# Ad_Hoc_Radio_Node_2005_v3.net
KiCad netlist of a schematic drawn in Altium Designer
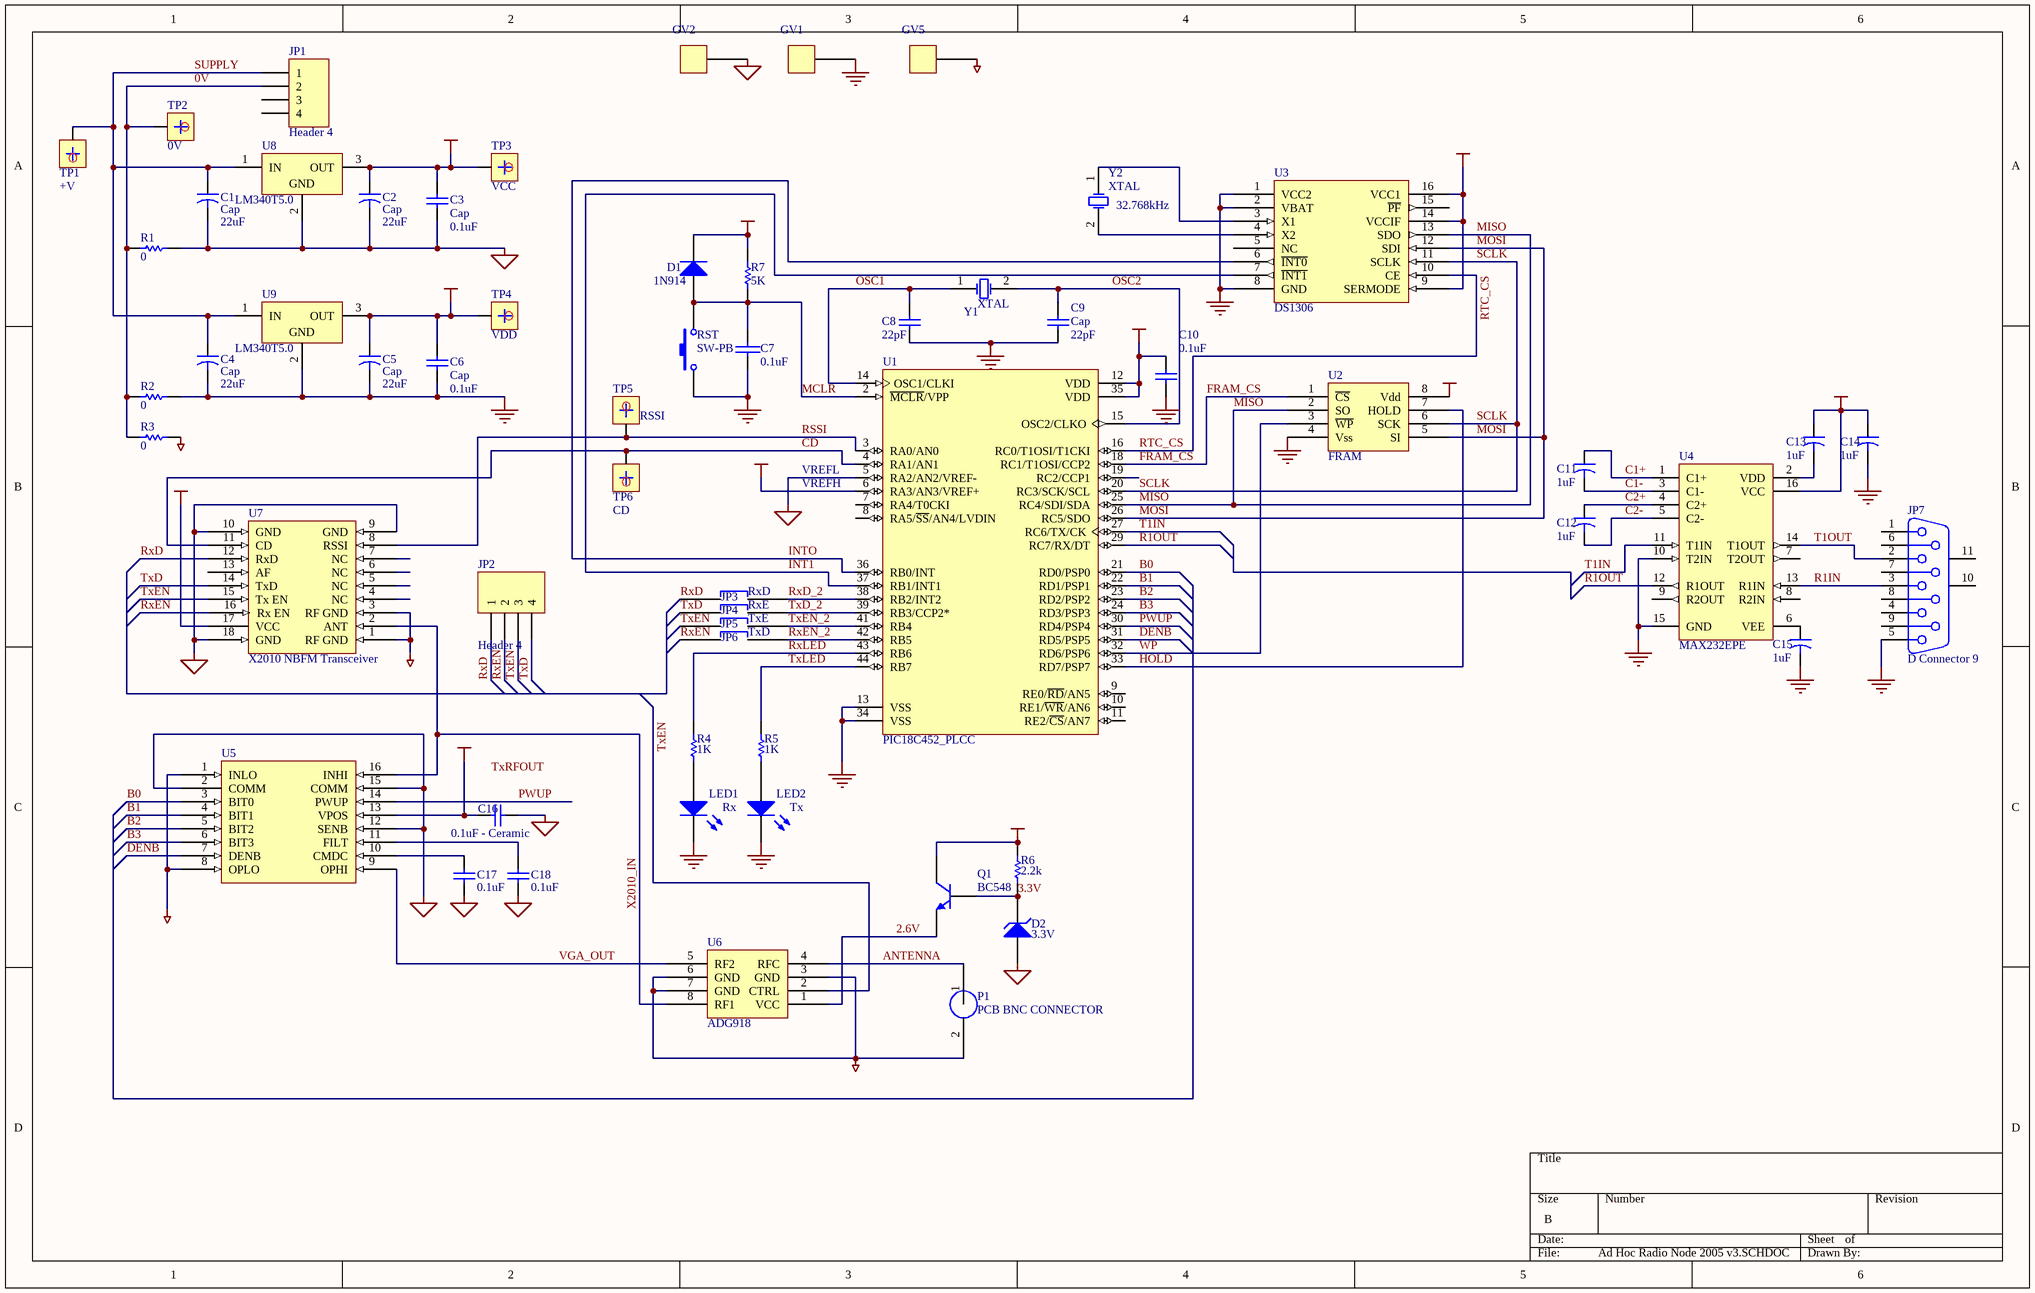
[diagram p0: Ad Hoc Radio Node 2005 v3.SCHDOC]

(export (version "E")
  (design (tool "Eeschema 10.0.6"))
  (components
    (comp (ref "C1")
      (value "Cap")
      (footprint "0.1 ELECTRO CAP")
      (description "Capacitor")
      (fields
        (field (name "MANUFACTURER") "Generic Components")
        (field (name "ALTIUM_VALUE") "22uF")
        (field (name "PUBLISHER") "Altium Limited")
      )
      (libsource (lib "Miscellaneous Devices") (part "Cap2"))
    )
    (comp (ref "C2")
      (value "Cap")
      (footprint "0.1 ELECTRO CAP")
      (description "Capacitor")
      (fields
        (field (name "MANUFACTURER") "Generic Components")
        (field (name "ALTIUM_VALUE") "22uF")
        (field (name "PUBLISHER") "Altium Limited")
      )
      (libsource (lib "Miscellaneous Devices") (part "Cap2"))
    )
    (comp (ref "C3")
      (value "Cap")
      (footprint "0.2 box cap")
      (description "Capacitor")
      (fields
        (field (name "MANUFACTURER") "Generic Components")
        (field (name "ALTIUM_VALUE") "0.1uF")
        (field (name "PUBLISHER") "Altium Limited")
      )
      (libsource (lib "Miscellaneous Devices") (part "Cap"))
    )
    (comp (ref "C4")
      (value "Cap")
      (footprint "0.1 ELECTRO CAP")
      (description "Capacitor")
      (fields
        (field (name "MANUFACTURER") "Generic Components")
        (field (name "ALTIUM_VALUE") "22uF")
        (field (name "PUBLISHER") "Altium Limited")
      )
      (libsource (lib "Miscellaneous Devices") (part "Cap2"))
    )
    (comp (ref "C5")
      (value "Cap")
      (footprint "0.1 ELECTRO CAP")
      (description "Capacitor")
      (fields
        (field (name "MANUFACTURER") "Generic Components")
        (field (name "ALTIUM_VALUE") "22uF")
        (field (name "PUBLISHER") "Altium Limited")
      )
      (libsource (lib "Miscellaneous Devices") (part "Cap2"))
    )
    (comp (ref "C6")
      (value "Cap")
      (footprint "0.2 box cap")
      (description "Capacitor")
      (fields
        (field (name "MANUFACTURER") "Generic Components")
        (field (name "ALTIUM_VALUE") "0.1uF")
        (field (name "PUBLISHER") "Altium Limited")
      )
      (libsource (lib "Miscellaneous Devices") (part "Cap"))
    )
    (comp (ref "C7")
      (value "0.1uF")
      (footprint "0.2 box cap")
      (description "Capacitor")
      (libsource (lib "*") (part "CAP"))
    )
    (comp (ref "C8")
      (value "Cap")
      (footprint "0.2 box cap")
      (description "Capacitor")
      (fields
        (field (name "MANUFACTURER") "Generic Components")
        (field (name "ALTIUM_VALUE") "22pF")
        (field (name "PUBLISHER") "Altium Limited")
      )
      (libsource (lib "Miscellaneous Devices") (part "Cap"))
    )
    (comp (ref "C9")
      (value "Cap")
      (footprint "0.2 box cap")
      (description "Capacitor")
      (fields
        (field (name "MANUFACTURER") "Generic Components")
        (field (name "ALTIUM_VALUE") "22pF")
        (field (name "PUBLISHER") "Altium Limited")
      )
      (libsource (lib "Miscellaneous Devices") (part "Cap"))
    )
    (comp (ref "C10")
      (value "0.1uF")
      (footprint "0.2 box cap")
      (description "Capacitor")
      (fields (field (name "MANUFACTURER") "Generic Components") (field (name "PUBLISHER") "Altium Limited"))
      (libsource (lib "Miscellaneous Devices") (part "Cap"))
    )
    (comp (ref "C11")
      (value "Cap2")
      (footprint "0.1 ELECTRO CAP")
      (description "Capacitor")
      (fields
        (field (name "MANUFACTURER") "Generic Components")
        (field (name "ALTIUM_VALUE") "1uF")
        (field (name "PUBLISHER") "Altium Limited")
      )
      (libsource (lib "Miscellaneous Devices") (part "Cap2"))
    )
    (comp (ref "C12")
      (value "Cap2")
      (footprint "0.1 ELECTRO CAP")
      (description "Capacitor")
      (fields
        (field (name "MANUFACTURER") "Generic Components")
        (field (name "ALTIUM_VALUE") "1uF")
        (field (name "PUBLISHER") "Altium Limited")
      )
      (libsource (lib "Miscellaneous Devices") (part "Cap2"))
    )
    (comp (ref "C13")
      (value "Cap2")
      (footprint "0.1 ELECTRO CAP")
      (description "Capacitor")
      (fields
        (field (name "MANUFACTURER") "Generic Components")
        (field (name "ALTIUM_VALUE") "1uF")
        (field (name "PUBLISHER") "Altium Limited")
      )
      (libsource (lib "Miscellaneous Devices") (part "Cap2"))
    )
    (comp (ref "C14")
      (value "Cap2")
      (footprint "0.1 ELECTRO CAP")
      (description "Capacitor")
      (fields
        (field (name "MANUFACTURER") "Generic Components")
        (field (name "ALTIUM_VALUE") "1uF")
        (field (name "PUBLISHER") "Altium Limited")
      )
      (libsource (lib "Miscellaneous Devices") (part "Cap2"))
    )
    (comp (ref "C15")
      (value "Cap2")
      (footprint "0.1 ELECTRO CAP")
      (description "Capacitor")
      (fields
        (field (name "MANUFACTURER") "Generic Components")
        (field (name "ALTIUM_VALUE") "1uF")
        (field (name "PUBLISHER") "Altium Limited")
      )
      (libsource (lib "Miscellaneous Devices") (part "Cap2"))
    )
    (comp (ref "C16")
      (value "0.1uF - Ceramic")
      (footprint "0.2 box cap")
      (description "Capacitor")
      (fields (field (name "MANUFACTURER") "Generic Components") (field (name "PUBLISHER") "Altium Limited"))
      (libsource (lib "Miscellaneous Devices") (part "Cap"))
    )
    (comp (ref "C17")
      (value "0.1uF")
      (footprint "0.2 box cap")
      (description "Capacitor")
      (fields (field (name "MANUFACTURER") "Generic Components") (field (name "PUBLISHER") "Altium Limited"))
      (libsource (lib "Miscellaneous Devices") (part "Cap"))
    )
    (comp (ref "C18")
      (value "0.1uF")
      (footprint "0.2 box cap")
      (description "Capacitor")
      (fields (field (name "MANUFACTURER") "Generic Components") (field (name "PUBLISHER") "Altium Limited"))
      (libsource (lib "Miscellaneous Devices") (part "Cap"))
    )
    (comp (ref "D1")
      (value "1N914")
      (footprint "diode-0.4/1.8")
      (description "Default Diode")
      (fields (field (name "MANUFACTURER") "Generic Components") (field (name "PUBLISHER") "Altium Limited"))
      (libsource (lib "Miscellaneous Devices") (part "Diode"))
    )
    (comp (ref "D2")
      (value "D Zener")
      (footprint "diode-0.4/1.8")
      (description "Zener Diode")
      (fields
        (field (name "MANUFACTURER") "Generic Components")
        (field (name "ALTIUM_VALUE") "3.3V")
        (field (name "PUBLISHER") "Altium Limited")
      )
      (libsource (lib "Miscellaneous Devices") (part "D Zener"))
    )
    (comp (ref "GV1") (value "GV") (footprint "GROUNDVIA") (libsource (lib "2005Parts") (part "GV")))
    (comp (ref "GV2") (value "GV") (footprint "GROUNDVIA") (libsource (lib "2005Parts") (part "GV")))
    (comp (ref "GV5") (value "GV") (footprint "GROUNDVIA") (libsource (lib "2005Parts") (part "GV")))
    (comp (ref "JP1")
      (value "Header 4")
      (footprint "4 Way Terminal Block")
      (description "Header, 4-Pin")
      (fields (field (name "MANUFACTURER") "Generic Components") (field (name "PUBLISHER") "Altium Limited"))
      (libsource (lib "Miscellaneous Connectors") (part "Header 4"))
    )
    (comp (ref "JP2")
      (value "Header 4")
      (footprint "4 Way Terminal Block")
      (description "Header, 4-Pin")
      (fields (field (name "MANUFACTURER") "Generic Components") (field (name "PUBLISHER") "Altium Limited"))
      (libsource (lib "") (part "Header 4_1"))
    )
    (comp (ref "JP3") (value "RxD") (footprint "JUMPER") (libsource (lib "2005Parts") (part "JUMPER")))
    (comp (ref "JP4") (value "RxE") (footprint "JUMPER") (libsource (lib "2005Parts") (part "JUMPER")))
    (comp (ref "JP5") (value "TxE") (footprint "JUMPER") (libsource (lib "2005Parts") (part "JUMPER")))
    (comp (ref "JP6") (value "TxD") (footprint "JUMPER") (libsource (lib "2005Parts") (part "JUMPER")))
    (comp (ref "JP7")
      (value "D Connector 9")
      (footprint "DSUB1.385-2H9")
      (description "Receptacle Assembly, 9 Position, Right Angle")
      (fields (field (name "MANUFACTURER") "Generic Components") (field (name "PUBLISHER") "Altium Limited"))
      (libsource (lib "Miscellaneous Connectors") (part "D Connector 9"))
    )
    (comp (ref "LED1")
      (value "Rx")
      (footprint "Std LED")
      (description "Typical RED, GREEN, YELLOW, AMBER GaAs LED")
      (fields (field (name "MANUFACTURER") "Generic Components") (field (name "PUBLISHER") "Altium Limited"))
      (libsource (lib "Miscellaneous Devices") (part "LED2"))
    )
    (comp (ref "LED2")
      (value "Tx")
      (footprint "Std LED")
      (description "Typical RED, GREEN, YELLOW, AMBER GaAs LED")
      (fields (field (name "MANUFACTURER") "Generic Components") (field (name "PUBLISHER") "Altium Limited"))
      (libsource (lib "Miscellaneous Devices") (part "LED2"))
    )
    (comp (ref "P1")
      (value "PCB BNC CONNECTOR")
      (footprint "PCB BNC Connector")
      (libsource (lib "2005Parts") (part "PCB BNC CONNECTOR"))
    )
    (comp (ref "Q1")
      (value "BC548")
      (footprint "bjt")
      (description "NPN Bipolar Transistor")
      (fields (field (name "MANUFACTURER") "Generic Components") (field (name "PUBLISHER") "Altium Limited"))
      (libsource (lib "Miscellaneous Devices") (part "NPN"))
    )
    (comp (ref "R1")
      (value "0")
      (footprint "AXIAL-0.3")
      (description "Resistor")
      (fields (field (name "MANUFACTURER") "Generic Components") (field (name "PUBLISHER") "Altium Limited"))
      (libsource (lib "Miscellaneous Devices") (part "Res1"))
    )
    (comp (ref "R2")
      (value "0")
      (footprint "AXIAL-0.3")
      (description "Resistor")
      (fields (field (name "MANUFACTURER") "Generic Components") (field (name "PUBLISHER") "Altium Limited"))
      (libsource (lib "Miscellaneous Devices") (part "Res1"))
    )
    (comp (ref "R3")
      (value "0")
      (footprint "AXIAL-0.3")
      (description "Resistor")
      (fields (field (name "MANUFACTURER") "Generic Components") (field (name "PUBLISHER") "Altium Limited"))
      (libsource (lib "Miscellaneous Devices") (part "Res1"))
    )
    (comp (ref "R4")
      (value "1K")
      (footprint "AXIAL-0.4/1.8")
      (description "Resistor")
      (fields (field (name "MANUFACTURER") "Generic Components") (field (name "PUBLISHER") "Altium Limited"))
      (libsource (lib "Miscellaneous Devices") (part "Res1"))
    )
    (comp (ref "R5")
      (value "1K")
      (footprint "AXIAL-0.4/1.8")
      (description "Resistor")
      (fields (field (name "MANUFACTURER") "Generic Components") (field (name "PUBLISHER") "Altium Limited"))
      (libsource (lib "Miscellaneous Devices") (part "Res1"))
    )
    (comp (ref "R6")
      (value "2.2k")
      (footprint "AXIAL-0.4/1.8")
      (description "Resistor")
      (fields (field (name "MANUFACTURER") "Generic Components") (field (name "PUBLISHER") "Altium Limited"))
      (libsource (lib "Miscellaneous Devices") (part "Res1"))
    )
    (comp (ref "R7")
      (value "Res1")
      (footprint "AXIAL-0.4/1.8")
      (description "Resistor")
      (fields
        (field (name "MANUFACTURER") "Generic Components")
        (field (name "ALTIUM_VALUE") "5K")
        (field (name "PUBLISHER") "Altium Limited")
      )
      (libsource (lib "Miscellaneous Devices") (part "Res1"))
    )
    (comp (ref "RST")
      (value "SW-PB")
      (footprint "Reset Switch - duplicate")
      (description "Switch")
      (fields (field (name "MANUFACTURER") "Generic Components") (field (name "PUBLISHER") "Altium Limited"))
      (libsource (lib "Miscellaneous Devices") (part "SW-PB"))
    )
    (comp (ref "TP1")
      (value "+V")
      (footprint "TESTPOINT")
      (description "Test Point")
      (libsource (lib "") (part "TESTPOINT_1"))
    )
    (comp (ref "TP2")
      (value "0V")
      (footprint "TESTPOINT")
      (description "Test Point")
      (libsource (lib "PeteSchLib") (part "TESTPOINT"))
    )
    (comp (ref "TP3")
      (value "VCC")
      (footprint "TESTPOINT")
      (description "Test Point")
      (libsource (lib "PeteSchLib") (part "TESTPOINT"))
    )
    (comp (ref "TP4")
      (value "VDD")
      (footprint "TESTPOINT")
      (description "Test Point")
      (libsource (lib "PeteSchLib") (part "TESTPOINT"))
    )
    (comp (ref "TP5")
      (value "RSSI")
      (footprint "TESTPOINT")
      (description "Test Point")
      (libsource (lib "") (part "TESTPOINT_2"))
    )
    (comp (ref "TP6")
      (value "CD")
      (footprint "TESTPOINT")
      (description "Test Point")
      (libsource (lib "") (part "TESTPOINT_1"))
    )
    (comp (ref "U1")
      (value "PIC18C452_PLCC")
      (footprint "PIC18C452_PLCC - duplicate")
      (libsource (lib "Ad_Hoc_Parts") (part "PIC18C452_PLCC"))
    )
    (comp (ref "U2") (value "FRAM") (footprint "Ramtron FRAM") (libsource (lib "Ad_Hoc_Parts") (part "FRAM")))
    (comp (ref "U3") (value "DS1306") (footprint "DIP-16") (libsource (lib "2005Parts") (part "DS1306")))
    (comp (ref "U4")
      (value "MAX232EPE")
      (footprint "DIP-16")
      (description "+5V Powered RS-232 Driver/Receiver")
      (fields (field (name "MANUFACTURER") "Maxim") (field (name "PUBLISHER") "Altium Limited"))
      (libsource (lib "Maxim Communication Transceiver") (part "MAX232EPE"))
    )
    (comp (ref "U5")
      (value "~")
      (footprint "DIP16-Adaptor")
      (libsource (lib "Ad_Hoc_Parts") (part "AD8369_DIGITAL_CONT_PWR_AMP"))
    )
    (comp (ref "U6") (value "ADG918") (footprint "DIP-8") (libsource (lib "2005Parts") (part "ADG918")))
    (comp (ref "U7")
      (value "X2010 NBFM Transceiver")
      (footprint "X2010")
      (libsource (lib "Ad_Hoc_Parts") (part "NBFM_TRANSCEIVER"))
    )
    (comp (ref "U8")
      (value "LM340T5.0")
      (footprint "SFM-T3/A4.7V")
      (description "Series 3-Terminal Positive Regulator")
      (fields
        (field (name "MANUFACTURER") "National Semiconductor")
        (field (name "PUBLISHER") "Altium Limited")
      )
      (libsource (lib "NSC Power Mgt Voltage Regulator") (part "LM340T5.0"))
    )
    (comp (ref "U9")
      (value "LM340T5.0")
      (footprint "SFM-T3/A4.7V")
      (description "Series 3-Terminal Positive Regulator")
      (fields
        (field (name "MANUFACTURER") "National Semiconductor")
        (field (name "PUBLISHER") "Altium Limited")
      )
      (libsource (lib "NSC Power Mgt Voltage Regulator") (part "LM340T5.0"))
    )
    (comp (ref "Y1")
      (value "XTAL")
      (footprint "XTAL")
      (description "Crystal Oscillator")
      (fields (field (name "MANUFACTURER") "Generic Components") (field (name "PUBLISHER") "Altium Limited"))
      (libsource (lib "Miscellaneous Devices") (part "XTAL"))
    )
    (comp (ref "Y2")
      (value "XTAL")
      (footprint "2005Parts:XTAL")
      (description "Crystal Oscillator")
      (fields
        (field (name "MANUFACTURER") "Generic Components")
        (field (name "ALTIUM_VALUE") "32.768kHz")
        (field (name "PUBLISHER") "Altium Limited")
      )
      (libsource (lib "Miscellaneous Devices") (part "XTAL"))
    )
  )
  (nets
    (net (code "1") (name "/0V") (class "Default")
      (node (ref "JP1") (pin "2") (pinfunction "2_2") (pintype "passive"))
      (node (ref "R1") (pin "1") (pinfunction "1_1") (pintype "passive"))
      (node (ref "R2") (pin "1") (pinfunction "1_1") (pintype "passive"))
      (node (ref "R3") (pin "1") (pinfunction "1_1") (pintype "passive"))
      (node (ref "TP2") (pin "1") (pinfunction "TP_1") (pintype "passive"))
    )
    (net (code "2") (name "/2.6V") (class "Default")
      (node (ref "Q1") (pin "3") (pinfunction "E_3") (pintype "passive"))
      (node (ref "U6") (pin "1") (pinfunction "VCC_1") (pintype "passive"))
    )
    (net (code "3") (name "/3.3V") (class "Default")
      (node (ref "D2") (pin "2") (pinfunction "K_2") (pintype "passive"))
      (node (ref "Q1") (pin "2") (pinfunction "B_2") (pintype "passive"))
      (node (ref "R6") (pin "2") (pinfunction "2_2") (pintype "passive"))
    )
    (net (code "4") (name "/ANTENNA") (class "Default")
      (node (ref "P1") (pin "1") (pinfunction "1_1") (pintype "passive"))
      (node (ref "U6") (pin "4") (pinfunction "RFC_4") (pintype "passive"))
    )
    (net (code "5") (name "/B0") (class "Default")
      (node (ref "U1") (pin "21") (pinfunction "RD0/PSP0_21") (pintype "bidirectional"))
      (node (ref "U5") (pin "3") (pinfunction "BIT0_3") (pintype "input"))
    )
    (net (code "6") (name "/B1") (class "Default")
      (node (ref "U1") (pin "22") (pinfunction "RD1/PSP1_22") (pintype "bidirectional"))
      (node (ref "U5") (pin "4") (pinfunction "BIT1_4") (pintype "input"))
    )
    (net (code "7") (name "/B2") (class "Default")
      (node (ref "U1") (pin "23") (pinfunction "RD2/PSP2_23") (pintype "bidirectional"))
      (node (ref "U5") (pin "5") (pinfunction "BIT2_5") (pintype "input"))
    )
    (net (code "8") (name "/B3") (class "Default")
      (node (ref "U1") (pin "24") (pinfunction "RD3/PSP3_24") (pintype "bidirectional"))
      (node (ref "U5") (pin "6") (pinfunction "BIT3_6") (pintype "input"))
    )
    (net (code "9") (name "/C1+") (class "Default")
      (node (ref "C11") (pin "1") (pinfunction "1_1") (pintype "passive"))
      (node (ref "U4") (pin "1") (pinfunction "C1+_1") (pintype "passive"))
    )
    (net (code "10") (name "/C1-") (class "Default")
      (node (ref "C11") (pin "2") (pinfunction "2_2") (pintype "passive"))
      (node (ref "U4") (pin "3") (pinfunction "C1-_3") (pintype "passive"))
    )
    (net (code "11") (name "/C2+") (class "Default")
      (node (ref "C12") (pin "1") (pinfunction "1_1") (pintype "passive"))
      (node (ref "U4") (pin "4") (pinfunction "C2+_4") (pintype "passive"))
    )
    (net (code "12") (name "/C2-") (class "Default")
      (node (ref "C12") (pin "2") (pinfunction "2_2") (pintype "passive"))
      (node (ref "U4") (pin "5") (pinfunction "C2-_5") (pintype "passive"))
    )
    (net (code "13") (name "/CD") (class "Default")
      (node (ref "TP6") (pin "1") (pinfunction "TP_1") (pintype "passive"))
      (node (ref "U1") (pin "4") (pinfunction "RA1/AN1_4") (pintype "bidirectional"))
      (node (ref "U7") (pin "11") (pinfunction "CD_11") (pintype "input"))
    )
    (net (code "14") (name "/DENB") (class "Default")
      (node (ref "U1") (pin "31") (pinfunction "RD5/PSP5_31") (pintype "bidirectional"))
      (node (ref "U5") (pin "7") (pinfunction "DENB_7") (pintype "input"))
    )
    (net (code "15") (name "/FRAM_CS") (class "Default")
      (node (ref "U1") (pin "18") (pinfunction "RC1/T1OSI/CCP2_18") (pintype "bidirectional"))
      (node (ref "U2") (pin "1") (pinfunction "~{CS}_1") (pintype "passive"))
    )
    (net (code "16") (name "/HOLD") (class "Default")
      (node (ref "U1") (pin "33") (pinfunction "RD7/PSP7_33") (pintype "bidirectional"))
      (node (ref "U2") (pin "7") (pinfunction "HOLD_7") (pintype "passive"))
    )
    (net (code "17") (name "/INT1") (class "Default")
      (node (ref "U1") (pin "37") (pinfunction "RB1/INT1_37") (pintype "bidirectional"))
      (node (ref "U3") (pin "7") (pinfunction "~{INT1}_7") (pintype "output"))
    )
    (net (code "18") (name "/INTO") (class "Default")
      (node (ref "U1") (pin "36") (pinfunction "RB0/INT_36") (pintype "bidirectional"))
      (node (ref "U3") (pin "6") (pinfunction "~{INT0}_6") (pintype "output"))
    )
    (net (code "19") (name "/MCLR") (class "Default")
      (node (ref "C7") (pin "1") (pinfunction "1_1") (pintype "passive"))
      (node (ref "D1") (pin "1") (pinfunction "A_1") (pintype "passive"))
      (node (ref "R7") (pin "1") (pinfunction "1_1") (pintype "passive"))
      (node (ref "RST") (pin "2") (pinfunction "2_2") (pintype "passive"))
      (node (ref "U1") (pin "2") (pinfunction "~{MCLR}/VPP_2") (pintype "input"))
    )
    (net (code "20") (name "/MISO") (class "Default")
      (node (ref "U1") (pin "25") (pinfunction "RC4/SDI/SDA_25") (pintype "bidirectional"))
      (node (ref "U2") (pin "2") (pinfunction "SO_2") (pintype "passive"))
      (node (ref "U3") (pin "13") (pinfunction "SDO_13") (pintype "output"))
    )
    (net (code "21") (name "/MOSI") (class "Default")
      (node (ref "U1") (pin "26") (pinfunction "RC5/SDO_26") (pintype "bidirectional"))
      (node (ref "U2") (pin "5") (pinfunction "SI_5") (pintype "passive"))
      (node (ref "U3") (pin "12") (pinfunction "SDI_12") (pintype "input"))
    )
    (net (code "22") (name "/OSC1") (class "Default")
      (node (ref "C8") (pin "2") (pinfunction "2_2") (pintype "passive"))
      (node (ref "U1") (pin "14") (pinfunction "OSC1/CLKI_14") (pintype "input"))
      (node (ref "Y1") (pin "1") (pinfunction "OSC1_1") (pintype "passive"))
    )
    (net (code "23") (name "/OSC2") (class "Default")
      (node (ref "C9") (pin "2") (pinfunction "2_2") (pintype "passive"))
      (node (ref "U1") (pin "15") (pinfunction "OSC2/CLKO_15") (pintype "output"))
      (node (ref "Y1") (pin "2") (pinfunction "OSC2_2") (pintype "passive"))
    )
    (net (code "24") (name "/PWUP") (class "Default")
      (node (ref "U1") (pin "30") (pinfunction "RD4/PSP4_30") (pintype "bidirectional"))
      (node (ref "U5") (pin "14") (pinfunction "PWUP_14") (pintype "input"))
    )
    (net (code "25") (name "/R1IN") (class "Default")
      (node (ref "JP7") (pin "3") (pinfunction "3_3") (pintype "passive"))
      (node (ref "U4") (pin "13") (pinfunction "R1IN_13") (pintype "input"))
    )
    (net (code "26") (name "/R1OUT") (class "Default")
      (node (ref "U1") (pin "29") (pinfunction "RC7/RX/DT_29") (pintype "bidirectional"))
      (node (ref "U4") (pin "12") (pinfunction "R1OUT_12") (pintype "output"))
    )
    (net (code "27") (name "/RSSI") (class "Default")
      (node (ref "TP5") (pin "1") (pinfunction "TP_1") (pintype "passive"))
      (node (ref "U1") (pin "3") (pinfunction "RA0/AN0_3") (pintype "bidirectional"))
      (node (ref "U7") (pin "8") (pinfunction "RSSI_8") (pintype "input"))
    )
    (net (code "28") (name "/RTC_CS") (class "Default")
      (node (ref "U1") (pin "16") (pinfunction "RC0/T1OSI/T1CKI_16") (pintype "bidirectional"))
      (node (ref "U3") (pin "10") (pinfunction "CE_10") (pintype "input"))
    )
    (net (code "29") (name "/RxD") (class "Default")
      (node (ref "JP2") (pin "1") (pinfunction "1_1") (pintype "passive"))
      (node (ref "JP3") (pin "1") (pinfunction "1_1") (pintype "passive"))
      (node (ref "U7") (pin "12") (pinfunction "RxD_12") (pintype "input"))
    )
    (net (code "30") (name "/RxD_2") (class "Default")
      (node (ref "JP3") (pin "2") (pinfunction "2_2") (pintype "passive"))
      (node (ref "U1") (pin "38") (pinfunction "RB2/INT2_38") (pintype "bidirectional"))
    )
    (net (code "31") (name "/RxEN") (class "Default")
      (node (ref "JP2") (pin "2") (pinfunction "2_2") (pintype "passive"))
      (node (ref "JP6") (pin "1") (pinfunction "1_1") (pintype "passive"))
      (node (ref "U7") (pin "16") (pinfunction "Rx_EN_16") (pintype "input"))
    )
    (net (code "32") (name "/RxEN_2") (class "Default")
      (node (ref "JP6") (pin "2") (pinfunction "2_2") (pintype "passive"))
      (node (ref "U1") (pin "42") (pinfunction "RB5_42") (pintype "bidirectional"))
    )
    (net (code "33") (name "/RxLED") (class "Default")
      (node (ref "R4") (pin "1") (pinfunction "1_1") (pintype "passive"))
      (node (ref "U1") (pin "43") (pinfunction "RB6_43") (pintype "bidirectional"))
    )
    (net (code "34") (name "/SCLK") (class "Default")
      (node (ref "U1") (pin "20") (pinfunction "RC3/SCK/SCL_20") (pintype "bidirectional"))
      (node (ref "U2") (pin "6") (pinfunction "SCK_6") (pintype "passive"))
      (node (ref "U3") (pin "11") (pinfunction "SCLK_11") (pintype "input"))
    )
    (net (code "35") (name "/SUPPLY") (class "Default")
      (node (ref "C1") (pin "1") (pinfunction "1_1") (pintype "passive"))
      (node (ref "C4") (pin "1") (pinfunction "1_1") (pintype "passive"))
      (node (ref "JP1") (pin "1") (pinfunction "1_1") (pintype "passive"))
      (node (ref "TP1") (pin "1") (pinfunction "TP_1") (pintype "passive"))
      (node (ref "U8") (pin "1") (pinfunction "IN_1") (pintype "power_in"))
      (node (ref "U9") (pin "1") (pinfunction "IN_1") (pintype "power_in"))
    )
    (net (code "36") (name "/T1IN") (class "Default")
      (node (ref "U1") (pin "27") (pinfunction "RC6/TX/CK_27") (pintype "bidirectional"))
      (node (ref "U4") (pin "11") (pinfunction "T1IN_11") (pintype "input"))
    )
    (net (code "37") (name "/T1OUT") (class "Default")
      (node (ref "JP7") (pin "2") (pinfunction "2_2") (pintype "passive"))
      (node (ref "U4") (pin "14") (pinfunction "T1OUT_14") (pintype "output"))
    )
    (net (code "38") (name "/TxD") (class "Default")
      (node (ref "JP2") (pin "4") (pinfunction "4_4") (pintype "passive"))
      (node (ref "JP4") (pin "1") (pinfunction "1_1") (pintype "passive"))
      (node (ref "U7") (pin "14") (pinfunction "TxD_14") (pintype "input"))
    )
    (net (code "39") (name "/TxD_2") (class "Default")
      (node (ref "JP4") (pin "2") (pinfunction "2_2") (pintype "passive"))
      (node (ref "U1") (pin "39") (pinfunction "RB3/CCP2*_39") (pintype "bidirectional"))
    )
    (net (code "40") (name "/TxEN") (class "Default")
      (node (ref "JP2") (pin "3") (pinfunction "3_3") (pintype "passive"))
      (node (ref "JP5") (pin "1") (pinfunction "1_1") (pintype "passive"))
      (node (ref "U6") (pin "2") (pinfunction "CTRL_2") (pintype "passive"))
      (node (ref "U7") (pin "15") (pinfunction "Tx_EN_15") (pintype "input"))
    )
    (net (code "41") (name "/TxEN_2") (class "Default")
      (node (ref "JP5") (pin "2") (pinfunction "2_2") (pintype "passive"))
      (node (ref "U1") (pin "41") (pinfunction "RB4_41") (pintype "bidirectional"))
    )
    (net (code "42") (name "/TxLED") (class "Default")
      (node (ref "R5") (pin "1") (pinfunction "1_1") (pintype "passive"))
      (node (ref "U1") (pin "44") (pinfunction "RB7_44") (pintype "bidirectional"))
    )
    (net (code "44") (name "/VGA_OUT") (class "Default")
      (node (ref "U5") (pin "9") (pinfunction "OPHI_9") (pintype "input"))
      (node (ref "U6") (pin "5") (pinfunction "RF2_5") (pintype "passive"))
    )
    (net (code "45") (name "/WP") (class "Default")
      (node (ref "U1") (pin "32") (pinfunction "RD6/PSP6_32") (pintype "bidirectional"))
      (node (ref "U2") (pin "3") (pinfunction "~{WP}_3") (pintype "passive"))
    )
    (net (code "46") (name "/X2010_IN") (class "Default")
      (node (ref "U5") (pin "16") (pinfunction "INHI_16") (pintype "input"))
      (node (ref "U6") (pin "8") (pinfunction "RF1_8") (pintype "passive"))
      (node (ref "U7") (pin "2") (pinfunction "ANT_2") (pintype "input"))
    )
    (net (code "47") (name "GND") (class "Default")
      (node (ref "C10") (pin "2") (pinfunction "2_2") (pintype "passive"))
      (node (ref "C14") (pin "2") (pinfunction "2_2") (pintype "passive"))
      (node (ref "C15") (pin "2") (pinfunction "2_2") (pintype "passive"))
      (node (ref "C4") (pin "2") (pinfunction "2_2") (pintype "passive"))
      (node (ref "C5") (pin "2") (pinfunction "2_2") (pintype "passive"))
      (node (ref "C6") (pin "2") (pinfunction "2_2") (pintype "passive"))
      (node (ref "C7") (pin "2") (pinfunction "2_2") (pintype "passive"))
      (node (ref "C8") (pin "1") (pinfunction "1_1") (pintype "passive"))
      (node (ref "C9") (pin "1") (pinfunction "1_1") (pintype "passive"))
      (node (ref "GV1") (pin "1") (pinfunction "9_1") (pintype "passive"))
      (node (ref "JP7") (pin "5") (pinfunction "5_5") (pintype "passive"))
      (node (ref "LED1") (pin "2") (pinfunction "K_2") (pintype "passive"))
      (node (ref "LED2") (pin "2") (pinfunction "K_2") (pintype "passive"))
      (node (ref "R2") (pin "2") (pinfunction "2_2") (pintype "passive"))
      (node (ref "RST") (pin "1") (pinfunction "1_1") (pintype "passive"))
      (node (ref "U1") (pin "13") (pinfunction "VSS_13") (pintype "power_in"))
      (node (ref "U1") (pin "34") (pinfunction "VSS_34") (pintype "power_in"))
      (node (ref "U2") (pin "4") (pinfunction "Vss_4") (pintype "passive"))
      (node (ref "U3") (pin "1") (pinfunction "VCC2_1") (pintype "power_in"))
      (node (ref "U3") (pin "2") (pinfunction "VBAT_2") (pintype "power_in"))
      (node (ref "U3") (pin "8") (pinfunction "GND_8") (pintype "power_in"))
      (node (ref "U4") (pin "10") (pinfunction "T2IN_10") (pintype "input"))
      (node (ref "U4") (pin "15") (pinfunction "GND_15") (pintype "power_in"))
      (node (ref "U9") (pin "2") (pinfunction "GND_2") (pintype "power_in"))
    )
    (net (code "48") (name "Net-(LED1-A)") (class "Default")
      (node (ref "LED1") (pin "1") (pinfunction "A_1") (pintype "passive"))
      (node (ref "R4") (pin "2") (pinfunction "2_2") (pintype "passive"))
    )
    (net (code "49") (name "Net-(LED2-A)") (class "Default")
      (node (ref "LED2") (pin "1") (pinfunction "A_1") (pintype "passive"))
      (node (ref "R5") (pin "2") (pinfunction "2_2") (pintype "passive"))
    )
    (net (code "50") (name "Net-(U3-X1)") (class "Default")
      (node (ref "U3") (pin "3") (pinfunction "X1_3") (pintype "input"))
      (node (ref "Y2") (pin "1") (pinfunction "OSC1_1") (pintype "passive"))
    )
    (net (code "51") (name "Net-(U3-X2)") (class "Default")
      (node (ref "U3") (pin "4") (pinfunction "X2_4") (pintype "input"))
      (node (ref "Y2") (pin "2") (pinfunction "OSC2_2") (pintype "passive"))
    )
    (net (code "52") (name "Net-(U4-VDD)") (class "Default")
      (node (ref "C13") (pin "2") (pinfunction "2_2") (pintype "passive"))
      (node (ref "U4") (pin "2") (pinfunction "VDD_2") (pintype "power_in"))
    )
    (net (code "53") (name "Net-(U4-VEE)") (class "Default")
      (node (ref "C15") (pin "1") (pinfunction "1_1") (pintype "passive"))
      (node (ref "U4") (pin "6") (pinfunction "VEE_6") (pintype "power_in"))
    )
    (net (code "54") (name "Net-(U5-CMDC)") (class "Default")
      (node (ref "C17") (pin "1") (pinfunction "1_1") (pintype "passive"))
      (node (ref "U5") (pin "10") (pinfunction "CMDC_10") (pintype "input"))
    )
    (net (code "55") (name "Net-(U5-FILT)") (class "Default")
      (node (ref "C18") (pin "1") (pinfunction "1_1") (pintype "passive"))
      (node (ref "U5") (pin "11") (pinfunction "FILT_11") (pintype "input"))
    )
    (net (code "56") (name "RFGND") (class "Default")
      (node (ref "GV5") (pin "1") (pinfunction "9_1") (pintype "passive"))
      (node (ref "P1") (pin "2") (pinfunction "2_2") (pintype "passive"))
      (node (ref "R3") (pin "2") (pinfunction "2_2") (pintype "passive"))
      (node (ref "U5") (pin "1") (pinfunction "INLO_1") (pintype "input"))
      (node (ref "U5") (pin "8") (pinfunction "OPLO_8") (pintype "input"))
      (node (ref "U6") (pin "3") (pinfunction "GND_3") (pintype "passive"))
      (node (ref "U6") (pin "6") (pinfunction "GND_6") (pintype "passive"))
      (node (ref "U6") (pin "7") (pinfunction "GND_7") (pintype "passive"))
      (node (ref "U7") (pin "1") (pinfunction "RF_GND_1") (pintype "input"))
      (node (ref "U7") (pin "3") (pinfunction "RF_GND_3") (pintype "input"))
    )
    (net (code "57") (name "SGND") (class "Default")
      (node (ref "C1") (pin "2") (pinfunction "2_2") (pintype "passive"))
      (node (ref "C16") (pin "1") (pinfunction "1_1") (pintype "passive"))
      (node (ref "C17") (pin "2") (pinfunction "2_2") (pintype "passive"))
      (node (ref "C18") (pin "2") (pinfunction "2_2") (pintype "passive"))
      (node (ref "C2") (pin "2") (pinfunction "2_2") (pintype "passive"))
      (node (ref "C3") (pin "2") (pinfunction "2_2") (pintype "passive"))
      (node (ref "D2") (pin "1") (pinfunction "A_1") (pintype "passive"))
      (node (ref "GV2") (pin "1") (pinfunction "9_1") (pintype "passive"))
      (node (ref "R1") (pin "2") (pinfunction "2_2") (pintype "passive"))
      (node (ref "U1") (pin "5") (pinfunction "RA2/AN2/VREF-_5") (pintype "bidirectional"))
      (node (ref "U5") (pin "12") (pinfunction "SENB_12") (pintype "input"))
      (node (ref "U5") (pin "15") (pinfunction "COMM_15") (pintype "input"))
      (node (ref "U5") (pin "2") (pinfunction "COMM_2") (pintype "power_in"))
      (node (ref "U7") (pin "10") (pinfunction "GND_10") (pintype "input"))
      (node (ref "U7") (pin "18") (pinfunction "GND_18") (pintype "input"))
      (node (ref "U7") (pin "9") (pinfunction "GND_9") (pintype "input"))
      (node (ref "U8") (pin "2") (pinfunction "GND_2") (pintype "power_in"))
    )
    (net (code "58") (name "VCC") (class "Default")
      (node (ref "C16") (pin "2") (pinfunction "2_2") (pintype "passive"))
      (node (ref "C2") (pin "1") (pinfunction "1_1") (pintype "passive"))
      (node (ref "C3") (pin "1") (pinfunction "1_1") (pintype "passive"))
      (node (ref "Q1") (pin "1") (pinfunction "C_1") (pintype "passive"))
      (node (ref "R6") (pin "1") (pinfunction "1_1") (pintype "passive"))
      (node (ref "TP3") (pin "1") (pinfunction "TP_1") (pintype "passive"))
      (node (ref "U1") (pin "6") (pinfunction "RA3/AN3/VREF+_6") (pintype "bidirectional"))
      (node (ref "U5") (pin "13") (pinfunction "VPOS_13") (pintype "input"))
      (node (ref "U7") (pin "17") (pinfunction "VCC_17") (pintype "power_in"))
      (node (ref "U8") (pin "3") (pinfunction "OUT_3") (pintype "power_in"))
    )
    (net (code "59") (name "VDD") (class "Default")
      (node (ref "C10") (pin "1") (pinfunction "1_1") (pintype "passive"))
      (node (ref "C13") (pin "1") (pinfunction "1_1") (pintype "passive"))
      (node (ref "C14") (pin "1") (pinfunction "1_1") (pintype "passive"))
      (node (ref "C5") (pin "1") (pinfunction "1_1") (pintype "passive"))
      (node (ref "C6") (pin "1") (pinfunction "1_1") (pintype "passive"))
      (node (ref "D1") (pin "2") (pinfunction "K_2") (pintype "passive"))
      (node (ref "R7") (pin "2") (pinfunction "2_2") (pintype "passive"))
      (node (ref "TP4") (pin "1") (pinfunction "TP_1") (pintype "passive"))
      (node (ref "U1") (pin "12") (pinfunction "VDD_12") (pintype "power_in"))
      (node (ref "U1") (pin "35") (pinfunction "VDD_35") (pintype "power_in"))
      (node (ref "U2") (pin "8") (pinfunction "Vdd_8") (pintype "passive"))
      (node (ref "U3") (pin "14") (pinfunction "VCCIF_14") (pintype "power_in"))
      (node (ref "U3") (pin "16") (pinfunction "VCC1_16") (pintype "power_in"))
      (node (ref "U3") (pin "9") (pinfunction "SERMODE_9") (pintype "input"))
      (node (ref "U4") (pin "16") (pinfunction "VCC_16") (pintype "power_in"))
      (node (ref "U9") (pin "3") (pinfunction "OUT_3") (pintype "power_in"))
    )
    (net (code "60") (name "unconnected-(JP1-Pad3)") (class "Default")
      (node (ref "JP1") (pin "3") (pinfunction "3_3") (pintype "passive"))
    )
    (net (code "61") (name "unconnected-(JP1-Pad4)") (class "Default")
      (node (ref "JP1") (pin "4") (pinfunction "4_4") (pintype "passive"))
    )
    (net (code "62") (name "unconnected-(JP7-MH1-Pad10)") (class "Default")
      (node (ref "JP7") (pin "10") (pinfunction "MH1_10") (pintype "passive"))
    )
    (net (code "63") (name "unconnected-(JP7-MH2-Pad11)") (class "Default")
      (node (ref "JP7") (pin "11") (pinfunction "MH2_11") (pintype "passive"))
    )
    (net (code "64") (name "unconnected-(JP7-Pad1)") (class "Default")
      (node (ref "JP7") (pin "1") (pinfunction "1_1") (pintype "passive"))
    )
    (net (code "65") (name "unconnected-(JP7-Pad4)") (class "Default")
      (node (ref "JP7") (pin "4") (pinfunction "4_4") (pintype "passive"))
    )
    (net (code "66") (name "unconnected-(JP7-Pad6)") (class "Default")
      (node (ref "JP7") (pin "6") (pinfunction "6_6") (pintype "passive"))
    )
    (net (code "67") (name "unconnected-(JP7-Pad7)") (class "Default")
      (node (ref "JP7") (pin "7") (pinfunction "7_7") (pintype "passive"))
    )
    (net (code "68") (name "unconnected-(JP7-Pad8)") (class "Default")
      (node (ref "JP7") (pin "8") (pinfunction "8_8") (pintype "passive"))
    )
    (net (code "69") (name "unconnected-(JP7-Pad9)") (class "Default")
      (node (ref "JP7") (pin "9") (pinfunction "9_9") (pintype "passive"))
    )
    (net (code "70") (name "unconnected-(U1-RA4{slash}T0CKI-Pad7)") (class "Default")
      (node (ref "U1") (pin "7") (pinfunction "RA4/T0CKI_7") (pintype "bidirectional"))
    )
    (net (code "71") (name "unconnected-(U1-RA5{slash}~{SS}{slash}AN4{slash}LVDIN-Pad8)") (class "Default")
      (node (ref "U1") (pin "8") (pinfunction "RA5/~{SS}/AN4/LVDIN_8") (pintype "bidirectional"))
    )
    (net (code "72") (name "unconnected-(U1-RC2{slash}CCP1-Pad19)") (class "Default")
      (node (ref "U1") (pin "19") (pinfunction "RC2/CCP1_19") (pintype "bidirectional"))
    )
    (net (code "73") (name "unconnected-(U1-RE0{slash}~{RD}{slash}AN5-Pad9)") (class "Default")
      (node (ref "U1") (pin "9") (pinfunction "RE0/~{RD}/AN5_9") (pintype "bidirectional"))
    )
    (net (code "74") (name "unconnected-(U1-RE1{slash}~{WR}{slash}AN6-Pad10)") (class "Default")
      (node (ref "U1") (pin "10") (pinfunction "RE1/~{WR}/AN6_10") (pintype "bidirectional"))
    )
    (net (code "75") (name "unconnected-(U1-RE2{slash}~{CS}{slash}AN7-Pad11)") (class "Default")
      (node (ref "U1") (pin "11") (pinfunction "RE2/~{CS}/AN7_11") (pintype "bidirectional"))
    )
    (net (code "76") (name "unconnected-(U3-NC-Pad5)") (class "Default")
      (node (ref "U3") (pin "5") (pinfunction "NC_5") (pintype "passive"))
    )
    (net (code "77") (name "unconnected-(U3-~{PF}-Pad15)") (class "Default")
      (node (ref "U3") (pin "15") (pinfunction "~{PF}_15") (pintype "output"))
    )
    (net (code "78") (name "unconnected-(U4-R2IN-Pad8)") (class "Default")
      (node (ref "U4") (pin "8") (pinfunction "R2IN_8") (pintype "input"))
    )
    (net (code "79") (name "unconnected-(U4-R2OUT-Pad9)") (class "Default")
      (node (ref "U4") (pin "9") (pinfunction "R2OUT_9") (pintype "output"))
    )
    (net (code "80") (name "unconnected-(U4-T2OUT-Pad7)") (class "Default")
      (node (ref "U4") (pin "7") (pinfunction "T2OUT_7") (pintype "output"))
    )
    (net (code "81") (name "unconnected-(U7-AF-Pad13)") (class "Default")
      (node (ref "U7") (pin "13") (pinfunction "AF_13") (pintype "input"))
    )
    (net (code "82") (name "unconnected-(U7-NC-Pad4)") (class "Default")
      (node (ref "U7") (pin "4") (pinfunction "NC_4") (pintype "input"))
    )
    (net (code "83") (name "unconnected-(U7-NC-Pad5)") (class "Default")
      (node (ref "U7") (pin "5") (pinfunction "NC_5") (pintype "input"))
    )
    (net (code "84") (name "unconnected-(U7-NC-Pad6)") (class "Default")
      (node (ref "U7") (pin "6") (pinfunction "NC_6") (pintype "input"))
    )
    (net (code "85") (name "unconnected-(U7-NC-Pad7)") (class "Default")
      (node (ref "U7") (pin "7") (pinfunction "NC_7") (pintype "input"))
    )
  )
)
